# Buck_Converter_12v.net
KiCad netlist of a schematic drawn in Altium Designer
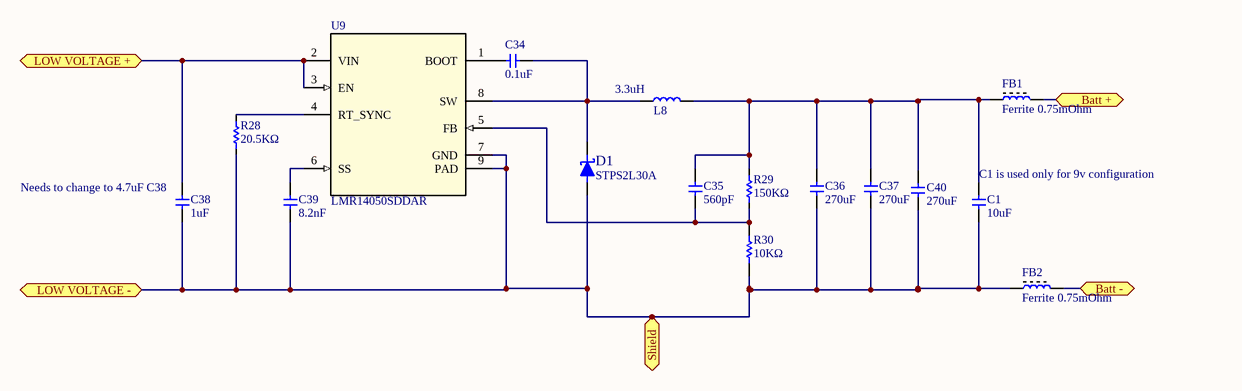
[diagram p0: Buck Converter_12v.SchDoc]

(export (version "E")
  (design (tool "Eeschema 10.0.6"))
  (components
    (comp (ref "C1")
      (value "10uF")
      (footprint "0805 capacitor")
      (description "10µF ±10% 16V Ceramic Capacitor X5R 0805 (2012 Metric)")
      (fields (field (name "MANUFACTURER") "Murata Electronics North America"))
      (libsource (lib "Curtis") (part "Cap"))
    )
    (comp (ref "C34")
      (value "0.1uF")
      (footprint "0805 capacitor")
      (description "CAP CER 0.1UF 50V 10% X7R 0603")
      (fields (field (name "MANUFACTURER") "KEMET"))
      (libsource (lib "Curtis") (part "Cap"))
    )
    (comp (ref "C35")
      (value "560pF")
      (footprint "0603 Capacitor")
      (description "CAP CER 560PF 25V X7R 0201")
      (fields (field (name "MANUFACTURER") "Murata Electronics North America"))
      (libsource (lib "Curtis") (part "Cap"))
    )
    (comp (ref "C36")
      (value "270uF")
      (footprint "APXG160ARA271MH70G")
      (description "CAP ALUM POLY 270UF 20% 16V SMD")
      (fields (field (name "MANUFACTURER") "United Chemi-Con"))
      (libsource (lib "Curtis") (part "Cap"))
    )
    (comp (ref "C37")
      (value "270uF")
      (footprint "APXG160ARA271MH70G")
      (description "CAP ALUM POLY 270UF 20% 16V SMD")
      (fields (field (name "MANUFACTURER") "United Chemi-Con"))
      (libsource (lib "Curtis") (part "Cap"))
    )
    (comp (ref "C38")
      (value "1uF")
      (footprint "1206 - duplicate")
      (description "1µF ±10% 50V Ceramic Capacitor X7R 0805 (2012 Metric)")
      (fields (field (name "MANUFACTURER") "Samsung Electro-Mechanics America, Inc."))
      (libsource (lib "Curtis") (part "Cap"))
    )
    (comp (ref "C39")
      (value "8.2nF")
      (footprint "0402 Small")
      (description "8200pF ±10% 16V Ceramic Capacitor X7R 0402 (1005 Metric)")
      (fields (field (name "MANUFACTURER") "Murata Electronics North America"))
      (libsource (lib "Curtis") (part "Cap"))
    )
    (comp (ref "C40")
      (value "270uF")
      (footprint "APXG160ARA271MH70G")
      (description "CAP ALUM POLY 270UF 20% 16V SMD")
      (fields (field (name "MANUFACTURER") "United Chemi-Con"))
      (libsource (lib "Curtis") (part "Cap"))
    )
    (comp (ref "D1")
      (value "STPS2L30A")
      (footprint "SMC")
      (description "DIODE SCHOTTKY 30V 2A SMA")
      (fields (field (name "MANUFACTURER") "STMICROELECTRONICS"))
      (libsource (lib "Curtis") (part "DIODE_SCHOTTKY"))
    )
    (comp (ref "FB1")
      (value "Ferrite 0.75mOhm")
      (footprint "2-SMD, J-LEAD")
      (description "FERRITE BEAD 48 OHM 2SMD 1LN")
      (fields (field (name "MANUFACTURER") "Laird-Signal Integrity Products"))
      (libsource (lib "Curtis") (part "Ferrite Bead"))
    )
    (comp (ref "FB2")
      (value "Ferrite 0.75mOhm")
      (footprint "2-SMD, J-LEAD")
      (description "FERRITE BEAD 48 OHM 2SMD 1LN")
      (fields (field (name "MANUFACTURER") "Laird-Signal Integrity Products"))
      (libsource (lib "Curtis") (part "Ferrite Bead"))
    )
    (comp (ref "L8")
      (value "3.3uH")
      (footprint "SRN8040 - Power Inductor")
      (description "Fixed Inductors XAL5030 High Current 3.3 uH 20 % 8.1 A")
      (fields (field (name "MANUFACTURER") "Coilcraft"))
      (libsource (lib "Curtis") (part "Inductor"))
    )
    (comp (ref "R28")
      (value "20.5KΩ")
      (footprint "0603")
      (description "20.5k Ohm ±1% 0.1W, 1/10W Chip Resistor 0603 (1608 Metric) Automotive AEC-Q200 Thick Film")
      (fields (field (name "MANUFACTURER") "Panasonic Electronic Components"))
      (libsource (lib "Curtis") (part "Resistor"))
    )
    (comp (ref "R29")
      (value "150KΩ")
      (footprint "0603 resistor")
      (description "RES SMD 150K OHM 1% 1/16W 0402")
      (fields (field (name "MANUFACTURER") "Vishay Dale"))
      (libsource (lib "Curtis") (part "Resistor"))
    )
    (comp (ref "R30")
      (value "10KΩ")
      (footprint "0805")
      (description "RES SMD 10K OHM 1% 1/8W 0805")
      (fields (field (name "MANUFACTURER") "Panasonic Electronic Components"))
      (libsource (lib "Miscellaneous Devices") (part "Res1"))
    )
    (comp (ref "U9")
      (value "LMR14050SDDAR")
      (footprint "SO8 - GROUND PAD")
      (fields
        (field (name "MANUFACTURER") "Texas Instruments")
        (field (name "ALTERNATE_PARTNUMBER") "LMR14050SDDA")
      )
      (libsource (lib "Curtis") (part "LMR14050SDDAR"))
    )
  )
  (nets
    (net (code "1") (name "/Batt +") (class "Default")
      (node (ref "FB1") (pin "2") (pinfunction "2_2") (pintype "passive"))
    )
    (net (code "2") (name "/Batt -") (class "Default")
      (node (ref "FB2") (pin "2") (pinfunction "2_2") (pintype "passive"))
    )
    (net (code "3") (name "/LOW VOLTAGE +") (class "Default")
      (node (ref "C38") (pin "1") (pinfunction "1_1") (pintype "passive"))
      (node (ref "U9") (pin "2") (pinfunction "VIN_2") (pintype "power_in"))
      (node (ref "U9") (pin "3") (pinfunction "EN_3") (pintype "input"))
    )
    (net (code "4") (name "/LOW VOLTAGE -") (class "Default")
      (node (ref "C1") (pin "2") (pinfunction "2_2") (pintype "passive"))
      (node (ref "C36") (pin "2") (pinfunction "2_2") (pintype "passive"))
      (node (ref "C37") (pin "2") (pinfunction "2_2") (pintype "passive"))
      (node (ref "C38") (pin "2") (pinfunction "2_2") (pintype "passive"))
      (node (ref "C39") (pin "2") (pinfunction "2_2") (pintype "passive"))
      (node (ref "C40") (pin "2") (pinfunction "2_2") (pintype "passive"))
      (node (ref "D1") (pin "1") (pinfunction "A_1") (pintype "passive"))
      (node (ref "FB2") (pin "1") (pinfunction "1_1") (pintype "passive"))
      (node (ref "R28") (pin "1") (pinfunction "1_1") (pintype "passive"))
      (node (ref "R30") (pin "1") (pinfunction "1_1") (pintype "passive"))
      (node (ref "U9") (pin "7") (pinfunction "GND_7") (pintype "power_in"))
      (node (ref "U9") (pin "9") (pinfunction "PAD_9") (pintype "power_in"))
    )
    (net (code "5") (name "Net-(C1-Pad1)") (class "Default")
      (node (ref "C1") (pin "1") (pinfunction "1_1") (pintype "passive"))
      (node (ref "C35") (pin "1") (pinfunction "1_1") (pintype "passive"))
      (node (ref "C36") (pin "1") (pinfunction "1_1") (pintype "passive"))
      (node (ref "C37") (pin "1") (pinfunction "1_1") (pintype "passive"))
      (node (ref "C40") (pin "1") (pinfunction "1_1") (pintype "passive"))
      (node (ref "FB1") (pin "1") (pinfunction "1_1") (pintype "passive"))
      (node (ref "L8") (pin "2") (pinfunction "2_2") (pintype "passive"))
      (node (ref "R29") (pin "2") (pinfunction "2_2") (pintype "passive"))
    )
    (net (code "6") (name "Net-(D1-K)") (class "Default")
      (node (ref "C34") (pin "1") (pinfunction "1_1") (pintype "passive"))
      (node (ref "D1") (pin "2") (pinfunction "K_2") (pintype "passive"))
      (node (ref "L8") (pin "1") (pinfunction "1_1") (pintype "passive"))
      (node (ref "U9") (pin "8") (pinfunction "SW_8") (pintype "power_in"))
    )
    (net (code "7") (name "Net-(U9-BOOT)") (class "Default")
      (node (ref "C34") (pin "2") (pinfunction "2_2") (pintype "passive"))
      (node (ref "U9") (pin "1") (pinfunction "BOOT_1") (pintype "passive"))
    )
    (net (code "8") (name "Net-(U9-FB)") (class "Default")
      (node (ref "C35") (pin "2") (pinfunction "2_2") (pintype "passive"))
      (node (ref "R29") (pin "1") (pinfunction "1_1") (pintype "passive"))
      (node (ref "R30") (pin "2") (pinfunction "2_2") (pintype "passive"))
      (node (ref "U9") (pin "5") (pinfunction "FB_5") (pintype "input"))
    )
    (net (code "9") (name "Net-(U9-RT_SYNC)") (class "Default")
      (node (ref "R28") (pin "2") (pinfunction "2_2") (pintype "passive"))
      (node (ref "U9") (pin "4") (pinfunction "RT_SYNC_4") (pintype "passive"))
    )
    (net (code "10") (name "Net-(U9-SS)") (class "Default")
      (node (ref "C39") (pin "1") (pinfunction "1_1") (pintype "passive"))
      (node (ref "U9") (pin "6") (pinfunction "SS_6") (pintype "input"))
    )
  )
)
